# Main.net
KiCad netlist of a schematic drawn in Altium Designer
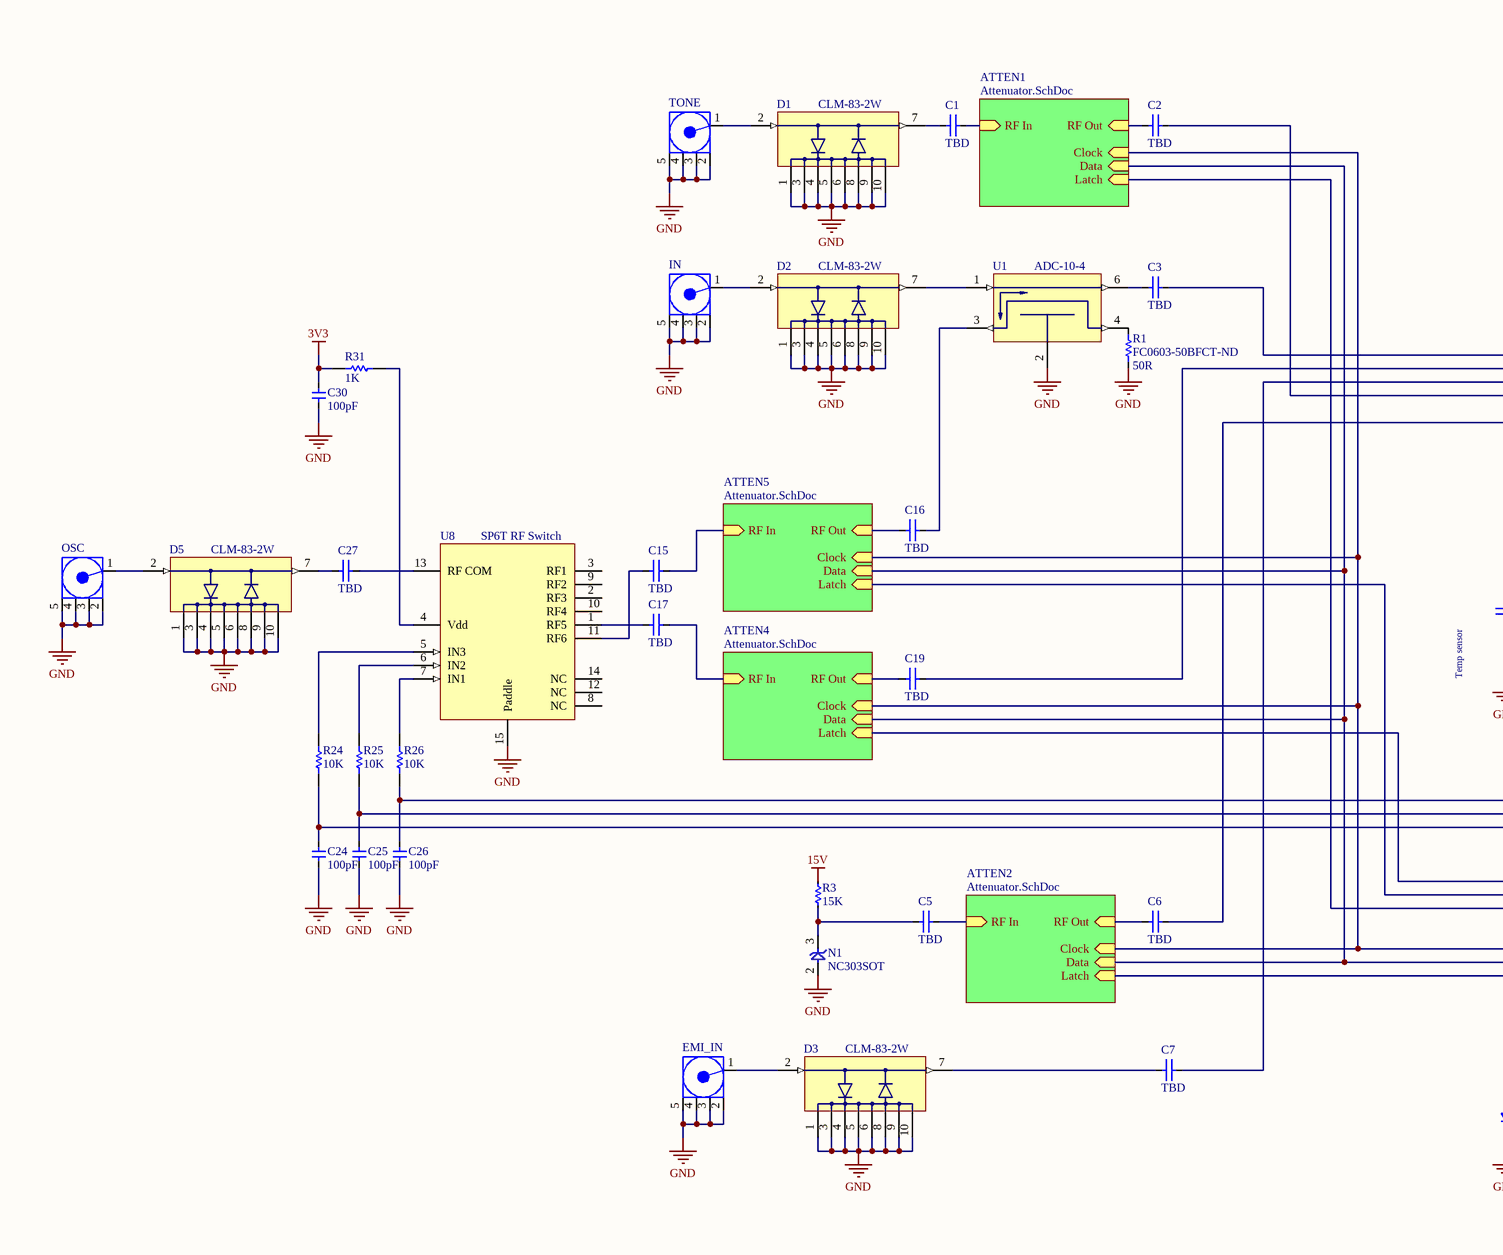
[diagram p0: Main.SchDoc, left]
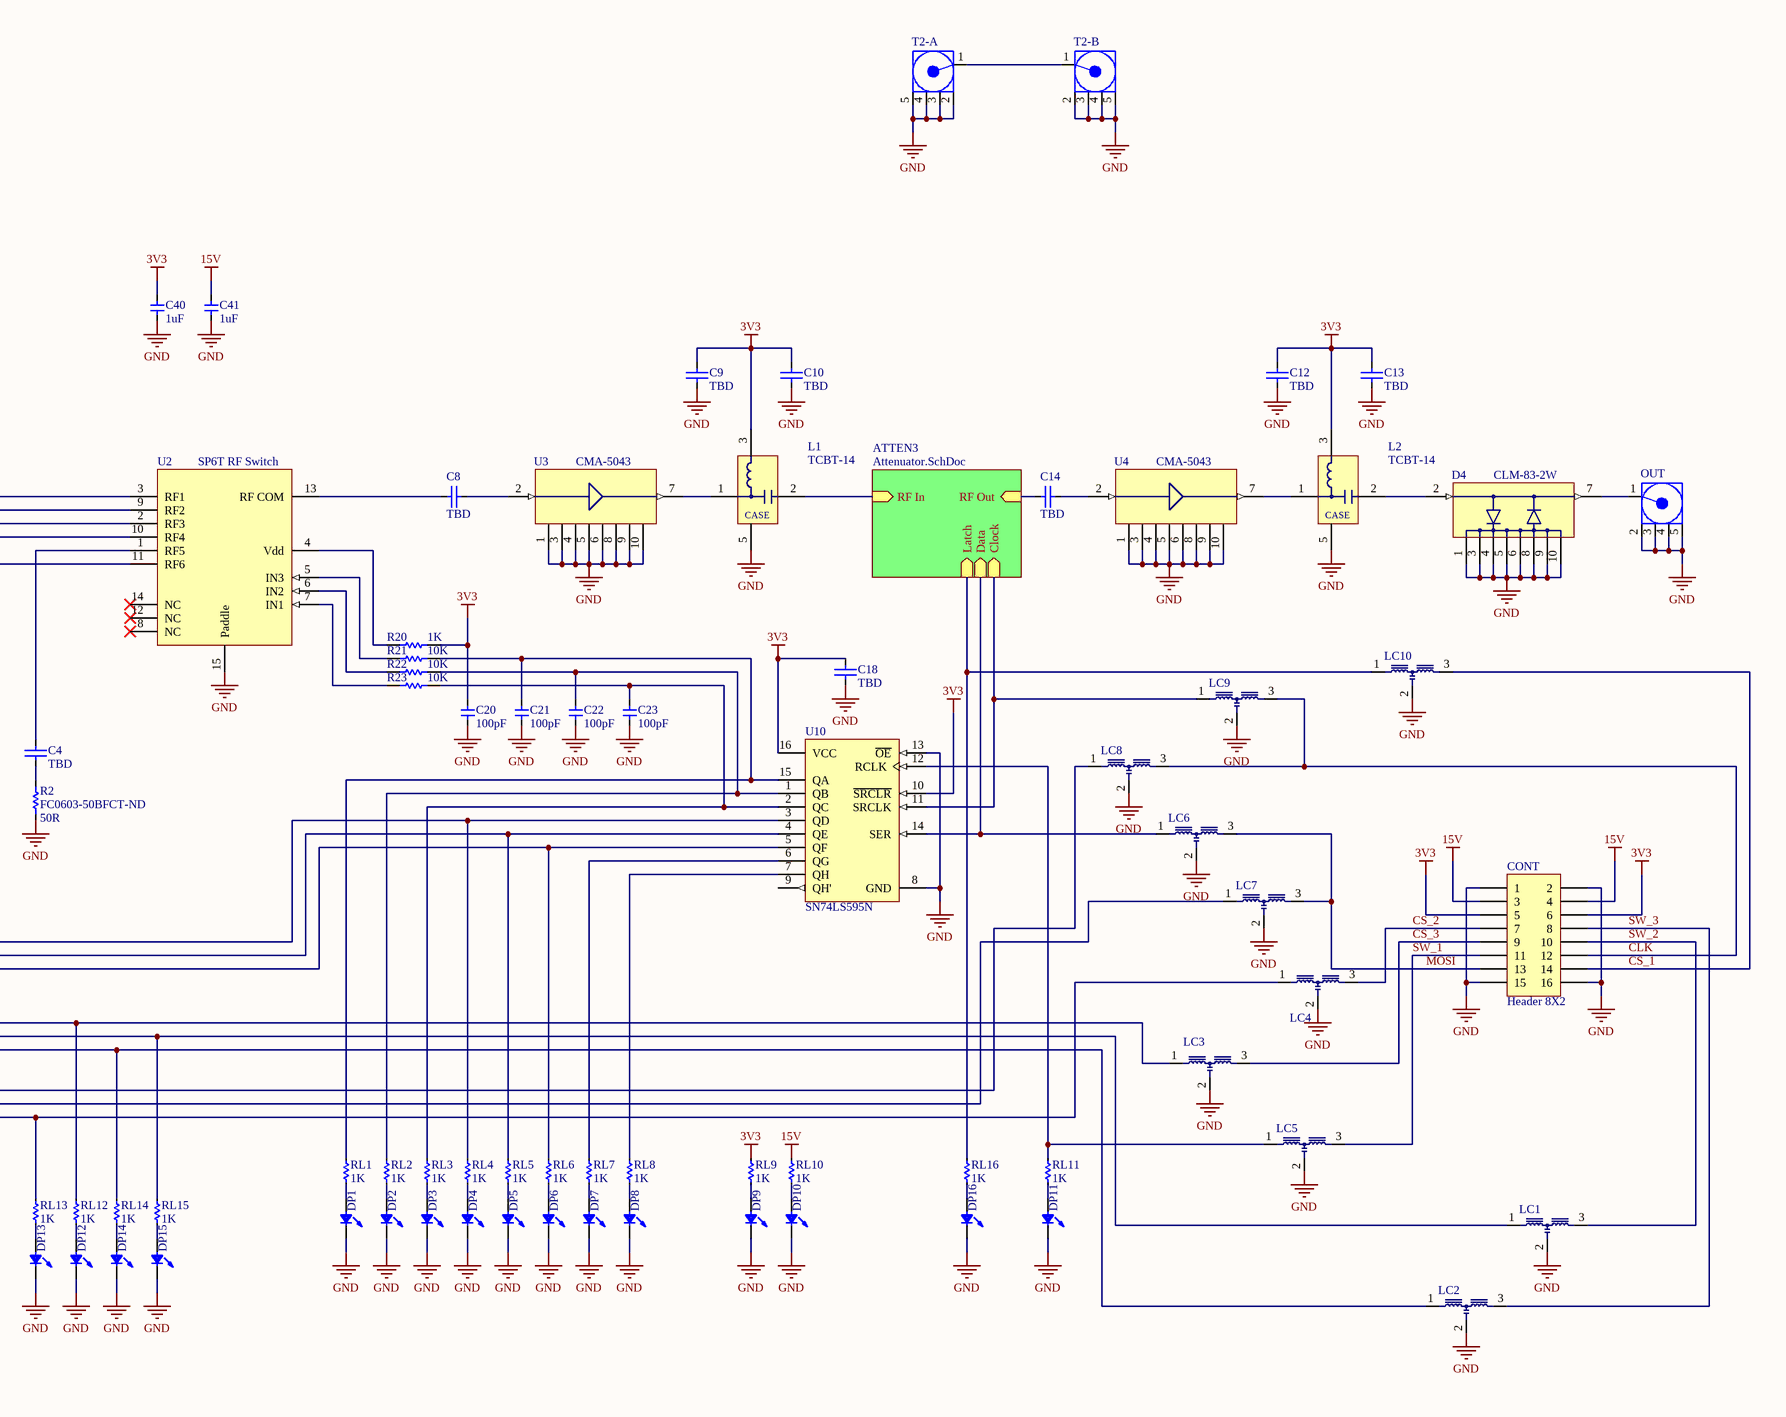
[diagram p1: Main.SchDoc, right]

(export (version "E")
  (design (tool "Eeschema 10.0.6"))
  (components
    (comp (ref "C1")
      (value "TBD")
      (footprint "0402C")
      (description "Capacitor")
      (fields (field (name "Comment") "Cap") (field (name "PUBLISHER") "Altium Limited"))
      (libsource (lib "Miscellaneous Devices") (part "Cap"))
    )
    (comp (ref "C2")
      (value "TBD")
      (footprint "0402C")
      (description "Capacitor")
      (fields (field (name "Comment") "Cap") (field (name "PUBLISHER") "Altium Limited"))
      (libsource (lib "Miscellaneous Devices") (part "Cap"))
    )
    (comp (ref "C3")
      (value "TBD")
      (footprint "0402C")
      (description "Capacitor")
      (fields (field (name "Comment") "Cap") (field (name "PUBLISHER") "Altium Limited"))
      (libsource (lib "Miscellaneous Devices") (part "Cap"))
    )
    (comp (ref "C4")
      (value "TBD")
      (footprint "0402C")
      (description "Capacitor")
      (fields (field (name "Comment") "Cap") (field (name "PUBLISHER") "Altium Limited"))
      (libsource (lib "Miscellaneous Devices") (part "Cap"))
    )
    (comp (ref "C5")
      (value "TBD")
      (footprint "0402C")
      (description "Capacitor")
      (fields (field (name "Comment") "Cap") (field (name "PUBLISHER") "Altium Limited"))
      (libsource (lib "Miscellaneous Devices") (part "Cap"))
    )
    (comp (ref "C6")
      (value "TBD")
      (footprint "0402C")
      (description "Capacitor")
      (fields (field (name "Comment") "Cap") (field (name "PUBLISHER") "Altium Limited"))
      (libsource (lib "Miscellaneous Devices") (part "Cap"))
    )
    (comp (ref "C7")
      (value "TBD")
      (footprint "0402C")
      (description "Capacitor")
      (fields (field (name "Comment") "Cap") (field (name "PUBLISHER") "Altium Limited"))
      (libsource (lib "Miscellaneous Devices") (part "Cap"))
    )
    (comp (ref "C8")
      (value "TBD")
      (footprint "0402C")
      (description "Capacitor")
      (fields (field (name "Comment") "Cap") (field (name "PUBLISHER") "Altium Limited"))
      (libsource (lib "Miscellaneous Devices") (part "Cap"))
    )
    (comp (ref "C9")
      (value "TBD")
      (footprint "0805C")
      (description "Capacitor")
      (fields (field (name "Comment") "Cap") (field (name "PUBLISHER") "Altium Limited"))
      (libsource (lib "Miscellaneous Devices") (part "Cap"))
    )
    (comp (ref "C10")
      (value "TBD")
      (footprint "0805C")
      (description "Capacitor")
      (fields (field (name "Comment") "Cap") (field (name "PUBLISHER") "Altium Limited"))
      (libsource (lib "Miscellaneous Devices") (part "Cap"))
    )
    (comp (ref "C12")
      (value "TBD")
      (footprint "0805C")
      (description "Capacitor")
      (fields (field (name "Comment") "Cap") (field (name "PUBLISHER") "Altium Limited"))
      (libsource (lib "Miscellaneous Devices") (part "Cap"))
    )
    (comp (ref "C13")
      (value "TBD")
      (footprint "0805C")
      (description "Capacitor")
      (fields (field (name "Comment") "Cap") (field (name "PUBLISHER") "Altium Limited"))
      (libsource (lib "Miscellaneous Devices") (part "Cap"))
    )
    (comp (ref "C14")
      (value "TBD")
      (footprint "0402C")
      (description "Capacitor")
      (fields (field (name "Comment") "Cap") (field (name "PUBLISHER") "Altium Limited"))
      (libsource (lib "Miscellaneous Devices") (part "Cap"))
    )
    (comp (ref "C15")
      (value "TBD")
      (footprint "0402C")
      (description "Capacitor")
      (fields (field (name "Comment") "Cap") (field (name "PUBLISHER") "Altium Limited"))
      (libsource (lib "Miscellaneous Devices") (part "Cap"))
    )
    (comp (ref "C16")
      (value "TBD")
      (footprint "0402C")
      (description "Capacitor")
      (fields (field (name "Comment") "Cap") (field (name "PUBLISHER") "Altium Limited"))
      (libsource (lib "Miscellaneous Devices") (part "Cap"))
    )
    (comp (ref "C17")
      (value "TBD")
      (footprint "0402C")
      (description "Capacitor")
      (fields (field (name "Comment") "Cap") (field (name "PUBLISHER") "Altium Limited"))
      (libsource (lib "Miscellaneous Devices") (part "Cap"))
    )
    (comp (ref "C18")
      (value "TBD")
      (footprint "0603C")
      (description "Capacitor")
      (fields (field (name "Comment") "Cap") (field (name "PUBLISHER") "Altium Limited"))
      (libsource (lib "Miscellaneous Devices") (part "Cap"))
    )
    (comp (ref "C19")
      (value "TBD")
      (footprint "0402C")
      (description "Capacitor")
      (fields (field (name "Comment") "Cap") (field (name "PUBLISHER") "Altium Limited"))
      (libsource (lib "Miscellaneous Devices") (part "Cap"))
    )
    (comp (ref "C20")
      (value "100pF")
      (footprint "0603C")
      (description "SMT Cap")
      (fields (field (name "PUBLISHER") "Altium Limited"))
      (libsource (lib "Miscellaneous Devices") (part "Cap - SMT Small"))
    )
    (comp (ref "C21")
      (value "100pF")
      (footprint "0603C")
      (description "SMT Cap")
      (fields (field (name "PUBLISHER") "Altium Limited"))
      (libsource (lib "Miscellaneous Devices") (part "Cap - SMT Small"))
    )
    (comp (ref "C22")
      (value "100pF")
      (footprint "0603C")
      (description "SMT Cap")
      (fields (field (name "PUBLISHER") "Altium Limited"))
      (libsource (lib "Miscellaneous Devices") (part "Cap - SMT Small"))
    )
    (comp (ref "C23")
      (value "100pF")
      (footprint "0603C")
      (description "SMT Cap")
      (fields (field (name "PUBLISHER") "Altium Limited"))
      (libsource (lib "Miscellaneous Devices") (part "Cap - SMT Small"))
    )
    (comp (ref "C24")
      (value "100pF")
      (footprint "0603C")
      (description "SMT Cap")
      (fields (field (name "PUBLISHER") "Altium Limited"))
      (libsource (lib "Miscellaneous Devices") (part "Cap - SMT Small"))
    )
    (comp (ref "C25")
      (value "100pF")
      (footprint "0603C")
      (description "SMT Cap")
      (fields (field (name "PUBLISHER") "Altium Limited"))
      (libsource (lib "Miscellaneous Devices") (part "Cap - SMT Small"))
    )
    (comp (ref "C26")
      (value "100pF")
      (footprint "0603C")
      (description "SMT Cap")
      (fields (field (name "PUBLISHER") "Altium Limited"))
      (libsource (lib "Miscellaneous Devices") (part "Cap - SMT Small"))
    )
    (comp (ref "C27")
      (value "TBD")
      (footprint "0402C")
      (description "Capacitor")
      (fields (field (name "Comment") "Cap") (field (name "PUBLISHER") "Altium Limited"))
      (libsource (lib "Miscellaneous Devices") (part "Cap"))
    )
    (comp (ref "C30")
      (value "100pF")
      (footprint "0603C")
      (description "SMT Cap")
      (fields (field (name "PUBLISHER") "Altium Limited"))
      (libsource (lib "Miscellaneous Devices") (part "Cap - SMT Small"))
    )
    (comp (ref "C40")
      (value "1uF")
      (footprint "V")
      (description "SMT Cap")
      (fields (field (name "PUBLISHER") "Altium Limited"))
      (libsource (lib "Miscellaneous Devices") (part "Cap - SMT Small"))
    )
    (comp (ref "C41")
      (value "1uF")
      (footprint "V")
      (description "SMT Cap")
      (fields (field (name "PUBLISHER") "Altium Limited"))
      (libsource (lib "Miscellaneous Devices") (part "Cap - SMT Small"))
    )
    (comp (ref "CONT")
      (value "Header 8X2")
      (footprint "SMT 16-pin rectangular header")
      (description "Header, 8-Pin, Dual row")
      (fields (field (name "PUBLISHER") "Altium Limited"))
      (libsource (lib "Miscellaneous Connectors") (part "Header 8X2"))
    )
    (comp (ref "D1")
      (value "CLM-83-2W")
      (footprint "DL1721")
      (description "+12 to +32 dBm RF Limiter")
      (libsource (lib "RF Components") (part "CLM-83-2W"))
    )
    (comp (ref "D2")
      (value "CLM-83-2W")
      (footprint "DL1721")
      (description "+12 to +32 dBm RF Limiter")
      (libsource (lib "RF Components") (part "CLM-83-2W"))
    )
    (comp (ref "D3")
      (value "CLM-83-2W")
      (footprint "DL1721")
      (description "+12 to +32 dBm RF Limiter")
      (libsource (lib "RF Components") (part "CLM-83-2W"))
    )
    (comp (ref "D4")
      (value "CLM-83-2W")
      (footprint "DL1721")
      (description "+12 to +32 dBm RF Limiter")
      (libsource (lib "RF Components") (part "CLM-83-2W"))
    )
    (comp (ref "D5")
      (value "CLM-83-2W")
      (footprint "DL1721")
      (description "+12 to +32 dBm RF Limiter")
      (libsource (lib "RF Components") (part "CLM-83-2W"))
    )
    (comp (ref "DP1")
      (value "LED0")
      (footprint "0603 SMT LED")
      (description "T 1 3/4 LED")
      (fields (field (name "PUBLISHER") "Altium Limited"))
      (libsource (lib "Miscellaneous Devices") (part "LED0"))
    )
    (comp (ref "DP2")
      (value "LED0")
      (footprint "0603 SMT LED")
      (description "T 1 3/4 LED")
      (fields (field (name "PUBLISHER") "Altium Limited"))
      (libsource (lib "Miscellaneous Devices") (part "LED0"))
    )
    (comp (ref "DP3")
      (value "LED0")
      (footprint "0603 SMT LED")
      (description "T 1 3/4 LED")
      (fields (field (name "PUBLISHER") "Altium Limited"))
      (libsource (lib "Miscellaneous Devices") (part "LED0"))
    )
    (comp (ref "DP4")
      (value "LED0")
      (footprint "0603 SMT LED")
      (description "T 1 3/4 LED")
      (fields (field (name "PUBLISHER") "Altium Limited"))
      (libsource (lib "Miscellaneous Devices") (part "LED0"))
    )
    (comp (ref "DP5")
      (value "LED0")
      (footprint "0603 SMT LED")
      (description "T 1 3/4 LED")
      (fields (field (name "PUBLISHER") "Altium Limited"))
      (libsource (lib "Miscellaneous Devices") (part "LED0"))
    )
    (comp (ref "DP6")
      (value "LED0")
      (footprint "0603 SMT LED")
      (description "T 1 3/4 LED")
      (fields (field (name "PUBLISHER") "Altium Limited"))
      (libsource (lib "Miscellaneous Devices") (part "LED0"))
    )
    (comp (ref "DP7")
      (value "LED0")
      (footprint "0603 SMT LED")
      (description "T 1 3/4 LED")
      (fields (field (name "PUBLISHER") "Altium Limited"))
      (libsource (lib "Miscellaneous Devices") (part "LED0"))
    )
    (comp (ref "DP8")
      (value "LED0")
      (footprint "0603 SMT LED")
      (description "T 1 3/4 LED")
      (fields (field (name "PUBLISHER") "Altium Limited"))
      (libsource (lib "Miscellaneous Devices") (part "LED0"))
    )
    (comp (ref "DP9")
      (value "LED0")
      (footprint "0603 SMT LED")
      (description "T 1 3/4 LED")
      (fields (field (name "PUBLISHER") "Altium Limited"))
      (libsource (lib "Miscellaneous Devices") (part "LED0"))
    )
    (comp (ref "DP10")
      (value "LED0")
      (footprint "0603 SMT LED")
      (description "T 1 3/4 LED")
      (fields (field (name "PUBLISHER") "Altium Limited"))
      (libsource (lib "Miscellaneous Devices") (part "LED0"))
    )
    (comp (ref "DP11")
      (value "LED0")
      (footprint "0603 SMT LED")
      (description "T 1 3/4 LED")
      (fields (field (name "PUBLISHER") "Altium Limited"))
      (libsource (lib "Miscellaneous Devices") (part "LED0"))
    )
    (comp (ref "DP12")
      (value "LED0")
      (footprint "0603 SMT LED")
      (description "T 1 3/4 LED")
      (fields (field (name "PUBLISHER") "Altium Limited"))
      (libsource (lib "Miscellaneous Devices") (part "LED0"))
    )
    (comp (ref "DP13")
      (value "LED0")
      (footprint "0603 SMT LED")
      (description "T 1 3/4 LED")
      (fields (field (name "PUBLISHER") "Altium Limited"))
      (libsource (lib "Miscellaneous Devices") (part "LED0"))
    )
    (comp (ref "DP14")
      (value "LED0")
      (footprint "0603 SMT LED")
      (description "T 1 3/4 LED")
      (fields (field (name "PUBLISHER") "Altium Limited"))
      (libsource (lib "Miscellaneous Devices") (part "LED0"))
    )
    (comp (ref "DP15")
      (value "LED0")
      (footprint "0603 SMT LED")
      (description "T 1 3/4 LED")
      (fields (field (name "PUBLISHER") "Altium Limited"))
      (libsource (lib "Miscellaneous Devices") (part "LED0"))
    )
    (comp (ref "DP16")
      (value "LED0")
      (footprint "0603 SMT LED")
      (description "T 1 3/4 LED")
      (fields (field (name "PUBLISHER") "Altium Limited"))
      (libsource (lib "Miscellaneous Devices") (part "LED0"))
    )
    (comp (ref "EMI_IN")
      (value "COAX-M")
      (footprint "SMT RA SMA Connector")
      (description "RF Coaxial PCB Connector, MMCX; Thru-Hole, Vertical Mount Plug,  50 Ohm Impedance")
      (fields (field (name "PUBLISHER") "Altium Limited"))
      (libsource (lib "Miscellaneous Connectors") (part "COAX-M"))
    )
    (comp (ref "IN")
      (value "COAX-M")
      (footprint "SMT RA SMA Connector")
      (description "RF Coaxial PCB Connector, MMCX; Thru-Hole, Vertical Mount Plug,  50 Ohm Impedance")
      (fields (field (name "PUBLISHER") "Altium Limited"))
      (libsource (lib "Miscellaneous Connectors") (part "COAX-M"))
    )
    (comp (ref "L1")
      (value "TCBT-14")
      (footprint "GU1414")
      (description "Surface Mount 10 MHz to 10 GHz Bias Tee")
      (libsource (lib "RF Components") (part "TCBT-14"))
    )
    (comp (ref "L2")
      (value "TCBT-14")
      (footprint "GU1414")
      (description "Surface Mount 10 MHz to 10 GHz Bias Tee")
      (libsource (lib "RF Components") (part "TCBT-14"))
    )
    (comp (ref "LC1")
      (value "MEM2012F")
      (footprint "MEM2012S LC Filter")
      (description "Signal Line 3-terminal Filters")
      (libsource (lib "Unsorted") (part "MEM2012F - Signal Filter"))
    )
    (comp (ref "LC2")
      (value "MEM2012F")
      (footprint "MEM2012S LC Filter")
      (description "Signal Line 3-terminal Filters")
      (libsource (lib "Unsorted") (part "MEM2012F - Signal Filter"))
    )
    (comp (ref "LC3")
      (value "MEM2012F")
      (footprint "MEM2012S LC Filter")
      (description "Signal Line 3-terminal Filters")
      (libsource (lib "Unsorted") (part "MEM2012F - Signal Filter"))
    )
    (comp (ref "LC4")
      (value "MEM2012F")
      (footprint "MEM2012S LC Filter")
      (description "Signal Line 3-terminal Filters")
      (libsource (lib "Unsorted") (part "MEM2012F - Signal Filter"))
    )
    (comp (ref "LC5")
      (value "MEM2012F")
      (footprint "MEM2012S LC Filter")
      (description "Signal Line 3-terminal Filters")
      (libsource (lib "Unsorted") (part "MEM2012F - Signal Filter"))
    )
    (comp (ref "LC6")
      (value "MEM2012F")
      (footprint "MEM2012S LC Filter")
      (description "Signal Line 3-terminal Filters")
      (libsource (lib "Unsorted") (part "MEM2012F - Signal Filter"))
    )
    (comp (ref "LC7")
      (value "MEM2012F")
      (footprint "MEM2012S LC Filter")
      (description "Signal Line 3-terminal Filters")
      (libsource (lib "Unsorted") (part "MEM2012F - Signal Filter"))
    )
    (comp (ref "LC8")
      (value "MEM2012F")
      (footprint "MEM2012S LC Filter")
      (description "Signal Line 3-terminal Filters")
      (libsource (lib "Unsorted") (part "MEM2012F - Signal Filter"))
    )
    (comp (ref "LC9")
      (value "MEM2012F")
      (footprint "MEM2012S LC Filter")
      (description "Signal Line 3-terminal Filters")
      (libsource (lib "Unsorted") (part "MEM2012F - Signal Filter"))
    )
    (comp (ref "LC10")
      (value "MEM2012F")
      (footprint "MEM2012S LC Filter")
      (description "Signal Line 3-terminal Filters")
      (libsource (lib "Unsorted") (part "MEM2012F - Signal Filter"))
    )
    (comp (ref "N1")
      (value "NC303SOT")
      (footprint "SOT323-3AN")
      (description "SMT Noise Diode")
      (libsource (lib "RF Components") (part "NC303SOT"))
    )
    (comp (ref "OSC")
      (value "COAX-M")
      (footprint "SMT RA SMA Connector")
      (description "RF Coaxial PCB Connector, MMCX; Thru-Hole, Vertical Mount Plug,  50 Ohm Impedance")
      (fields (field (name "PUBLISHER") "Altium Limited"))
      (libsource (lib "Miscellaneous Connectors") (part "COAX-M"))
    )
    (comp (ref "OUT")
      (value "COAX-M")
      (footprint "SMT RA SMA Connector")
      (description "RF Coaxial PCB Connector, MMCX; Thru-Hole, Vertical Mount Plug,  50 Ohm Impedance")
      (fields (field (name "PUBLISHER") "Altium Limited"))
      (libsource (lib "Miscellaneous Connectors") (part "COAX-M"))
    )
    (comp (ref "R1")
      (value "FC0603-50BFCT-ND")
      (footprint "0603R")
      (fields (field (name "ALTIUM_VALUE") "50R") (field (name "PUBLISHER") "Altium Limited"))
      (libsource (lib "") (part "Res Semi_1"))
    )
    (comp (ref "R2")
      (value "FC0603-50BFCT-ND")
      (footprint "0603R")
      (fields (field (name "ALTIUM_VALUE") "50R") (field (name "PUBLISHER") "Altium Limited"))
      (libsource (lib "") (part "Res Semi_1"))
    )
    (comp (ref "R3")
      (value "15K")
      (footprint "1206R")
      (description "Semiconductor Resistor")
      (fields (field (name "Comment") "Res Semi Small") (field (name "PUBLISHER") "Altium Limited"))
      (libsource (lib "Miscellaneous Devices") (part "Res Semi Small"))
    )
    (comp (ref "R20")
      (value "1K")
      (footprint "0603R")
      (description "Semiconductor Resistor")
      (fields (field (name "Comment") "RES Semi") (field (name "PUBLISHER") "Altium Limited"))
      (libsource (lib "Miscellaneous Devices") (part "Res Semi"))
    )
    (comp (ref "R21")
      (value "10K")
      (footprint "0603R")
      (description "Semiconductor Resistor")
      (fields (field (name "Comment") "RES Semi") (field (name "PUBLISHER") "Altium Limited"))
      (libsource (lib "Miscellaneous Devices") (part "Res Semi"))
    )
    (comp (ref "R22")
      (value "10K")
      (footprint "0603R")
      (description "Semiconductor Resistor")
      (fields (field (name "Comment") "RES Semi") (field (name "PUBLISHER") "Altium Limited"))
      (libsource (lib "Miscellaneous Devices") (part "Res Semi"))
    )
    (comp (ref "R23")
      (value "10K")
      (footprint "0603R")
      (description "Semiconductor Resistor")
      (fields (field (name "Comment") "RES Semi") (field (name "PUBLISHER") "Altium Limited"))
      (libsource (lib "Miscellaneous Devices") (part "Res Semi"))
    )
    (comp (ref "R24")
      (value "10K")
      (footprint "0603R")
      (description "Semiconductor Resistor")
      (fields (field (name "Comment") "RES Semi") (field (name "PUBLISHER") "Altium Limited"))
      (libsource (lib "Miscellaneous Devices") (part "Res Semi"))
    )
    (comp (ref "R25")
      (value "10K")
      (footprint "0603R")
      (description "Semiconductor Resistor")
      (fields (field (name "Comment") "RES Semi") (field (name "PUBLISHER") "Altium Limited"))
      (libsource (lib "Miscellaneous Devices") (part "Res Semi"))
    )
    (comp (ref "R26")
      (value "10K")
      (footprint "0603R")
      (description "Semiconductor Resistor")
      (fields (field (name "Comment") "RES Semi") (field (name "PUBLISHER") "Altium Limited"))
      (libsource (lib "Miscellaneous Devices") (part "Res Semi"))
    )
    (comp (ref "R31")
      (value "1K")
      (footprint "0603R")
      (description "Semiconductor Resistor")
      (fields (field (name "Comment") "RES Semi") (field (name "PUBLISHER") "Altium Limited"))
      (libsource (lib "Miscellaneous Devices") (part "Res Semi"))
    )
    (comp (ref "RL1")
      (value "1K")
      (footprint "0603R")
      (description "Semiconductor Resistor")
      (fields (field (name "Comment") "Res Semi Small") (field (name "PUBLISHER") "Altium Limited"))
      (libsource (lib "Miscellaneous Devices") (part "Res Semi Small"))
    )
    (comp (ref "RL2")
      (value "1K")
      (footprint "0603R")
      (description "Semiconductor Resistor")
      (fields (field (name "Comment") "Res Semi Small") (field (name "PUBLISHER") "Altium Limited"))
      (libsource (lib "Miscellaneous Devices") (part "Res Semi Small"))
    )
    (comp (ref "RL3")
      (value "1K")
      (footprint "0603R")
      (description "Semiconductor Resistor")
      (fields (field (name "Comment") "Res Semi Small") (field (name "PUBLISHER") "Altium Limited"))
      (libsource (lib "Miscellaneous Devices") (part "Res Semi Small"))
    )
    (comp (ref "RL4")
      (value "1K")
      (footprint "0603R")
      (description "Semiconductor Resistor")
      (fields (field (name "Comment") "Res Semi Small") (field (name "PUBLISHER") "Altium Limited"))
      (libsource (lib "Miscellaneous Devices") (part "Res Semi Small"))
    )
    (comp (ref "RL5")
      (value "1K")
      (footprint "0603R")
      (description "Semiconductor Resistor")
      (fields (field (name "Comment") "Res Semi Small") (field (name "PUBLISHER") "Altium Limited"))
      (libsource (lib "Miscellaneous Devices") (part "Res Semi Small"))
    )
    (comp (ref "RL6")
      (value "1K")
      (footprint "0603R")
      (description "Semiconductor Resistor")
      (fields (field (name "Comment") "Res Semi Small") (field (name "PUBLISHER") "Altium Limited"))
      (libsource (lib "Miscellaneous Devices") (part "Res Semi Small"))
    )
    (comp (ref "RL7")
      (value "1K")
      (footprint "0603R")
      (description "Semiconductor Resistor")
      (fields (field (name "Comment") "Res Semi Small") (field (name "PUBLISHER") "Altium Limited"))
      (libsource (lib "Miscellaneous Devices") (part "Res Semi Small"))
    )
    (comp (ref "RL8")
      (value "1K")
      (footprint "0603R")
      (description "Semiconductor Resistor")
      (fields (field (name "Comment") "Res Semi Small") (field (name "PUBLISHER") "Altium Limited"))
      (libsource (lib "Miscellaneous Devices") (part "Res Semi Small"))
    )
    (comp (ref "RL9")
      (value "1K")
      (footprint "0603R")
      (description "Semiconductor Resistor")
      (fields (field (name "Comment") "Res Semi Small") (field (name "PUBLISHER") "Altium Limited"))
      (libsource (lib "Miscellaneous Devices") (part "Res Semi Small"))
    )
    (comp (ref "RL10")
      (value "1K")
      (footprint "0603R")
      (description "Semiconductor Resistor")
      (fields (field (name "Comment") "Res Semi Small") (field (name "PUBLISHER") "Altium Limited"))
      (libsource (lib "Miscellaneous Devices") (part "Res Semi Small"))
    )
    (comp (ref "RL11")
      (value "1K")
      (footprint "0603R")
      (description "Semiconductor Resistor")
      (fields (field (name "Comment") "Res Semi Small") (field (name "PUBLISHER") "Altium Limited"))
      (libsource (lib "Miscellaneous Devices") (part "Res Semi Small"))
    )
    (comp (ref "RL12")
      (value "1K")
      (footprint "0603R")
      (description "Semiconductor Resistor")
      (fields (field (name "Comment") "Res Semi Small") (field (name "PUBLISHER") "Altium Limited"))
      (libsource (lib "Miscellaneous Devices") (part "Res Semi Small"))
    )
    (comp (ref "RL13")
      (value "1K")
      (footprint "0603R")
      (description "Semiconductor Resistor")
      (fields (field (name "Comment") "Res Semi Small") (field (name "PUBLISHER") "Altium Limited"))
      (libsource (lib "Miscellaneous Devices") (part "Res Semi Small"))
    )
    (comp (ref "RL14")
      (value "1K")
      (footprint "0603R")
      (description "Semiconductor Resistor")
      (fields (field (name "Comment") "Res Semi Small") (field (name "PUBLISHER") "Altium Limited"))
      (libsource (lib "Miscellaneous Devices") (part "Res Semi Small"))
    )
    (comp (ref "RL15")
      (value "1K")
      (footprint "0603R")
      (description "Semiconductor Resistor")
      (fields (field (name "Comment") "Res Semi Small") (field (name "PUBLISHER") "Altium Limited"))
      (libsource (lib "Miscellaneous Devices") (part "Res Semi Small"))
    )
    (comp (ref "RL16")
      (value "1K")
      (footprint "0603R")
      (description "Semiconductor Resistor")
      (fields (field (name "Comment") "Res Semi Small") (field (name "PUBLISHER") "Altium Limited"))
      (libsource (lib "Miscellaneous Devices") (part "Res Semi Small"))
    )
    (comp (ref "T2-A")
      (value "COAX-M")
      (footprint "SMT RA SMA Connector")
      (description "RF Coaxial PCB Connector, MMCX; Thru-Hole, Vertical Mount Plug,  50 Ohm Impedance")
      (fields (field (name "PUBLISHER") "Altium Limited"))
      (libsource (lib "Miscellaneous Connectors") (part "COAX-M"))
    )
    (comp (ref "T2-B")
      (value "COAX-M")
      (footprint "SMT RA SMA Connector")
      (description "RF Coaxial PCB Connector, MMCX; Thru-Hole, Vertical Mount Plug,  50 Ohm Impedance")
      (fields (field (name "PUBLISHER") "Altium Limited"))
      (libsource (lib "Miscellaneous Connectors") (part "COAX-M"))
    )
    (comp (ref "TONE")
      (value "COAX-M")
      (footprint "SMT RA SMA Connector")
      (description "RF Coaxial PCB Connector, MMCX; Thru-Hole, Vertical Mount Plug,  50 Ohm Impedance")
      (fields (field (name "PUBLISHER") "Altium Limited"))
      (libsource (lib "Miscellaneous Connectors") (part "COAX-M"))
    )
    (comp (ref "U1")
      (value "ADC-10-4")
      (footprint "CD542")
      (description "Surface Mount Directional Coupler")
      (libsource (lib "RF Components") (part "ADC-10-4"))
    )
    (comp (ref "U2")
      (value "SP6T RF Switch")
      (footprint "MT1817")
      (description "SP6T RF Switch 50Ω 10 to 2700 MHz")
      (libsource (lib "") (part "JSW6-33DR+_1"))
    )
    (comp (ref "U3")
      (value "CMA-5043")
      (footprint "DL1721")
      (description "Low Noise, High IP3 Monolithic Amplifier")
      (libsource (lib "RF Components") (part "CMA-5043"))
    )
    (comp (ref "U4")
      (value "CMA-5043")
      (footprint "DL1721")
      (description "Low Noise, High IP3 Monolithic Amplifier")
      (libsource (lib "RF Components") (part "CMA-5043"))
    )
    (comp (ref "U8")
      (value "SP6T RF Switch")
      (footprint "MT1817")
      (description "SP6T RF Switch 50Ω 10 to 2700 MHz")
      (libsource (lib "RF Components") (part "JSW6-33DR+"))
    )
    (comp (ref "U10")
      (value "SN74LS595N")
      (footprint "SOIC127P602-16BN")
      (description "8-Bit Shift Register with Output Latch")
      (fields (field (name "PUBLISHER") "Altium Limited"))
      (libsource (lib "TI Logic Register") (part "SN74LS595N"))
    )
  )
  (nets
    (net (code "1") (name "/CLK") (class "Default")
      (node (ref "CONT") (pin "12") (pinfunction "12_12") (pintype "passive"))
      (node (ref "LC8") (pin "3") (pinfunction "3_3") (pintype "passive"))
      (node (ref "LC9") (pin "3") (pinfunction "3_3") (pintype "passive"))
    )
    (net (code "2") (name "/CS_1") (class "Default")
      (node (ref "CONT") (pin "14") (pinfunction "14_14") (pintype "passive"))
      (node (ref "LC10") (pin "3") (pinfunction "3_3") (pintype "passive"))
    )
    (net (code "3") (name "/CS_2") (class "Default")
      (node (ref "CONT") (pin "7") (pinfunction "7_7") (pintype "passive"))
      (node (ref "LC4") (pin "3") (pinfunction "3_3") (pintype "passive"))
    )
    (net (code "4") (name "/CS_3") (class "Default")
      (node (ref "CONT") (pin "9") (pinfunction "9_9") (pintype "passive"))
      (node (ref "LC3") (pin "3") (pinfunction "3_3") (pintype "passive"))
    )
    (net (code "5") (name "/Clock") (class "Default")
      (node (ref "LC8") (pin "1") (pinfunction "1_1") (pintype "passive"))
    )
    (net (code "6") (name "/Clock_1") (class "Default")
      (node (ref "LC9") (pin "1") (pinfunction "1_1") (pintype "passive"))
      (node (ref "U10") (pin "11") (pinfunction "SRCLK_11") (pintype "input"))
    )
    (net (code "7") (name "/Data") (class "Default")
      (node (ref "LC7") (pin "1") (pinfunction "1_1") (pintype "passive"))
    )
    (net (code "8") (name "/Data_1") (class "Default")
      (node (ref "LC6") (pin "1") (pinfunction "1_1") (pintype "passive"))
      (node (ref "U10") (pin "14") (pinfunction "SER_14") (pintype "input"))
    )
    (net (code "9") (name "/Latch") (class "Default")
      (node (ref "LC2") (pin "1") (pinfunction "1_1") (pintype "passive"))
      (node (ref "RL14") (pin "1") (pinfunction "1_1") (pintype "passive"))
    )
    (net (code "10") (name "/Latch_1") (class "Default")
      (node (ref "LC10") (pin "1") (pinfunction "1_1") (pintype "passive"))
      (node (ref "RL16") (pin "1") (pinfunction "1_1") (pintype "passive"))
    )
    (net (code "11") (name "/Latch_2") (class "Default")
      (node (ref "LC4") (pin "1") (pinfunction "1_1") (pintype "passive"))
      (node (ref "RL13") (pin "1") (pinfunction "1_1") (pintype "passive"))
    )
    (net (code "12") (name "/Latch_3") (class "Default")
      (node (ref "LC3") (pin "1") (pinfunction "1_1") (pintype "passive"))
      (node (ref "RL12") (pin "1") (pinfunction "1_1") (pintype "passive"))
    )
    (net (code "13") (name "/Latch_4") (class "Default")
      (node (ref "LC1") (pin "1") (pinfunction "1_1") (pintype "passive"))
      (node (ref "RL15") (pin "1") (pinfunction "1_1") (pintype "passive"))
    )
    (net (code "14") (name "/MOSI") (class "Default")
      (node (ref "CONT") (pin "13") (pinfunction "13_13") (pintype "passive"))
      (node (ref "LC6") (pin "3") (pinfunction "3_3") (pintype "passive"))
      (node (ref "LC7") (pin "3") (pinfunction "3_3") (pintype "passive"))
    )
    (net (code "15") (name "/RF In") (class "Default")
      (node (ref "C1") (pin "2") (pinfunction "2_2") (pintype "passive"))
    )
    (net (code "16") (name "/RF In_1") (class "Default")
      (node (ref "L1") (pin "2") (pinfunction "RF_2") (pintype "passive"))
    )
    (net (code "17") (name "/RF In_2") (class "Default")
      (node (ref "C17") (pin "2") (pinfunction "2_2") (pintype "passive"))
    )
    (net (code "18") (name "/RF In_3") (class "Default")
      (node (ref "C15") (pin "2") (pinfunction "2_2") (pintype "passive"))
    )
    (net (code "19") (name "/RF In_4") (class "Default")
      (node (ref "C5") (pin "2") (pinfunction "2_2") (pintype "passive"))
    )
    (net (code "20") (name "/RF Out") (class "Default")
      (node (ref "C2") (pin "1") (pinfunction "1_1") (pintype "passive"))
    )
    (net (code "21") (name "/RF Out_1") (class "Default")
      (node (ref "C14") (pin "1") (pinfunction "1_1") (pintype "passive"))
    )
    (net (code "22") (name "/RF Out_2") (class "Default")
      (node (ref "C16") (pin "1") (pinfunction "1_1") (pintype "passive"))
    )
    (net (code "23") (name "/RF Out_3") (class "Default")
      (node (ref "C19") (pin "1") (pinfunction "1_1") (pintype "passive"))
    )
    (net (code "24") (name "/RF Out_4") (class "Default")
      (node (ref "C6") (pin "1") (pinfunction "1_1") (pintype "passive"))
    )
    (net (code "25") (name "/SW_1") (class "Default")
      (node (ref "CONT") (pin "11") (pinfunction "11_11") (pintype "passive"))
      (node (ref "LC5") (pin "3") (pinfunction "3_3") (pintype "passive"))
    )
    (net (code "26") (name "/SW_2") (class "Default")
      (node (ref "CONT") (pin "10") (pinfunction "10_10") (pintype "passive"))
      (node (ref "LC1") (pin "3") (pinfunction "3_3") (pintype "passive"))
    )
    (net (code "27") (name "/SW_3") (class "Default")
      (node (ref "CONT") (pin "8") (pinfunction "8_8") (pintype "passive"))
      (node (ref "LC2") (pin "3") (pinfunction "3_3") (pintype "passive"))
    )
    (net (code "28") (name "3V3") (class "Default")
      (node (ref "C10") (pin "2") (pinfunction "2_2") (pintype "passive"))
      (node (ref "C12") (pin "2") (pinfunction "2_2") (pintype "passive"))
      (node (ref "C13") (pin "2") (pinfunction "2_2") (pintype "passive"))
      (node (ref "C18") (pin "2") (pinfunction "2_2") (pintype "passive"))
      (node (ref "C20") (pin "2") (pinfunction "2_2") (pintype "passive"))
      (node (ref "C30") (pin "2") (pinfunction "2_2") (pintype "passive"))
      (node (ref "C40") (pin "1") (pinfunction "1_1") (pintype "passive"))
      (node (ref "C9") (pin "2") (pinfunction "2_2") (pintype "passive"))
      (node (ref "CONT") (pin "5") (pinfunction "5_5") (pintype "passive"))
      (node (ref "CONT") (pin "6") (pinfunction "6_6") (pintype "passive"))
      (node (ref "L1") (pin "3") (pinfunction "DC_3") (pintype "passive"))
      (node (ref "L2") (pin "3") (pinfunction "DC_3") (pintype "passive"))
      (node (ref "R20") (pin "2") (pinfunction "2_2") (pintype "passive"))
      (node (ref "R31") (pin "2") (pinfunction "2_2") (pintype "passive"))
      (node (ref "RL9") (pin "1") (pinfunction "1_1") (pintype "passive"))
      (node (ref "U10") (pin "10") (pinfunction "~{SRCLR}_10") (pintype "input"))
      (node (ref "U10") (pin "16") (pinfunction "VCC_16") (pintype "power_in"))
    )
    (net (code "29") (name "15V") (class "Default")
      (node (ref "C41") (pin "1") (pinfunction "1_1") (pintype "passive"))
      (node (ref "CONT") (pin "3") (pinfunction "3_3") (pintype "passive"))
      (node (ref "CONT") (pin "4") (pinfunction "4_4") (pintype "passive"))
      (node (ref "R3") (pin "2") (pinfunction "2_2") (pintype "passive"))
      (node (ref "RL10") (pin "1") (pinfunction "1_1") (pintype "passive"))
    )
    (net (code "30") (name "GND") (class "Default")
      (node (ref "C10") (pin "1") (pinfunction "1_1") (pintype "passive"))
      (node (ref "C12") (pin "1") (pinfunction "1_1") (pintype "passive"))
      (node (ref "C13") (pin "1") (pinfunction "1_1") (pintype "passive"))
      (node (ref "C18") (pin "1") (pinfunction "1_1") (pintype "passive"))
      (node (ref "C20") (pin "1") (pinfunction "1_1") (pintype "passive"))
      (node (ref "C21") (pin "1") (pinfunction "1_1") (pintype "passive"))
      (node (ref "C22") (pin "1") (pinfunction "1_1") (pintype "passive"))
      (node (ref "C23") (pin "1") (pinfunction "1_1") (pintype "passive"))
      (node (ref "C24") (pin "1") (pinfunction "1_1") (pintype "passive"))
      (node (ref "C25") (pin "1") (pinfunction "1_1") (pintype "passive"))
      (node (ref "C26") (pin "1") (pinfunction "1_1") (pintype "passive"))
      (node (ref "C30") (pin "1") (pinfunction "1_1") (pintype "passive"))
      (node (ref "C40") (pin "2") (pinfunction "2_2") (pintype "passive"))
      (node (ref "C41") (pin "2") (pinfunction "2_2") (pintype "passive"))
      (node (ref "C9") (pin "1") (pinfunction "1_1") (pintype "passive"))
      (node (ref "CONT") (pin "1") (pinfunction "1_1") (pintype "passive"))
      (node (ref "CONT") (pin "15") (pinfunction "15_15") (pintype "passive"))
      (node (ref "CONT") (pin "16") (pinfunction "16_16") (pintype "passive"))
      (node (ref "CONT") (pin "2") (pinfunction "2_2") (pintype "passive"))
      (node (ref "D1") (pin "1") (pinfunction "Gnd_1") (pintype "passive"))
      (node (ref "D1") (pin "10") (pinfunction "Gnd_10") (pintype "power_in"))
      (node (ref "D1") (pin "3") (pinfunction "Gnd_3") (pintype "power_in"))
      (node (ref "D1") (pin "4") (pinfunction "Gnd_4") (pintype "power_in"))
      (node (ref "D1") (pin "5") (pinfunction "Gnd_5") (pintype "power_in"))
      (node (ref "D1") (pin "6") (pinfunction "Gnd_6") (pintype "power_in"))
      (node (ref "D1") (pin "8") (pinfunction "Gnd_8") (pintype "power_in"))
      (node (ref "D1") (pin "9") (pinfunction "Gnd_9") (pintype "power_in"))
      (node (ref "D2") (pin "1") (pinfunction "Gnd_1") (pintype "passive"))
      (node (ref "D2") (pin "10") (pinfunction "Gnd_10") (pintype "power_in"))
      (node (ref "D2") (pin "3") (pinfunction "Gnd_3") (pintype "power_in"))
      (node (ref "D2") (pin "4") (pinfunction "Gnd_4") (pintype "power_in"))
      (node (ref "D2") (pin "5") (pinfunction "Gnd_5") (pintype "power_in"))
      (node (ref "D2") (pin "6") (pinfunction "Gnd_6") (pintype "power_in"))
      (node (ref "D2") (pin "8") (pinfunction "Gnd_8") (pintype "power_in"))
      (node (ref "D2") (pin "9") (pinfunction "Gnd_9") (pintype "power_in"))
      (node (ref "D3") (pin "1") (pinfunction "Gnd_1") (pintype "passive"))
      (node (ref "D3") (pin "10") (pinfunction "Gnd_10") (pintype "power_in"))
      (node (ref "D3") (pin "3") (pinfunction "Gnd_3") (pintype "power_in"))
      (node (ref "D3") (pin "4") (pinfunction "Gnd_4") (pintype "power_in"))
      (node (ref "D3") (pin "5") (pinfunction "Gnd_5") (pintype "power_in"))
      (node (ref "D3") (pin "6") (pinfunction "Gnd_6") (pintype "power_in"))
      (node (ref "D3") (pin "8") (pinfunction "Gnd_8") (pintype "power_in"))
      (node (ref "D3") (pin "9") (pinfunction "Gnd_9") (pintype "power_in"))
      (node (ref "D4") (pin "1") (pinfunction "Gnd_1") (pintype "passive"))
      (node (ref "D4") (pin "10") (pinfunction "Gnd_10") (pintype "power_in"))
      (node (ref "D4") (pin "3") (pinfunction "Gnd_3") (pintype "power_in"))
      (node (ref "D4") (pin "4") (pinfunction "Gnd_4") (pintype "power_in"))
      (node (ref "D4") (pin "5") (pinfunction "Gnd_5") (pintype "power_in"))
      (node (ref "D4") (pin "6") (pinfunction "Gnd_6") (pintype "power_in"))
      (node (ref "D4") (pin "8") (pinfunction "Gnd_8") (pintype "power_in"))
      (node (ref "D4") (pin "9") (pinfunction "Gnd_9") (pintype "power_in"))
      (node (ref "D5") (pin "1") (pinfunction "Gnd_1") (pintype "passive"))
      (node (ref "D5") (pin "10") (pinfunction "Gnd_10") (pintype "power_in"))
      (node (ref "D5") (pin "3") (pinfunction "Gnd_3") (pintype "power_in"))
      (node (ref "D5") (pin "4") (pinfunction "Gnd_4") (pintype "power_in"))
      (node (ref "D5") (pin "5") (pinfunction "Gnd_5") (pintype "power_in"))
      (node (ref "D5") (pin "6") (pinfunction "Gnd_6") (pintype "power_in"))
      (node (ref "D5") (pin "8") (pinfunction "Gnd_8") (pintype "power_in"))
      (node (ref "D5") (pin "9") (pinfunction "Gnd_9") (pintype "power_in"))
      (node (ref "DP1") (pin "2") (pinfunction "2_2") (pintype "passive"))
      (node (ref "DP10") (pin "2") (pinfunction "2_2") (pintype "passive"))
      (node (ref "DP11") (pin "2") (pinfunction "2_2") (pintype "passive"))
      (node (ref "DP12") (pin "2") (pinfunction "2_2") (pintype "passive"))
      (node (ref "DP13") (pin "2") (pinfunction "2_2") (pintype "passive"))
      (node (ref "DP14") (pin "2") (pinfunction "2_2") (pintype "passive"))
      (node (ref "DP15") (pin "2") (pinfunction "2_2") (pintype "passive"))
      (node (ref "DP16") (pin "2") (pinfunction "2_2") (pintype "passive"))
      (node (ref "DP2") (pin "2") (pinfunction "2_2") (pintype "passive"))
      (node (ref "DP3") (pin "2") (pinfunction "2_2") (pintype "passive"))
      (node (ref "DP4") (pin "2") (pinfunction "2_2") (pintype "passive"))
      (node (ref "DP5") (pin "2") (pinfunction "2_2") (pintype "passive"))
      (node (ref "DP6") (pin "2") (pinfunction "2_2") (pintype "passive"))
      (node (ref "DP7") (pin "2") (pinfunction "2_2") (pintype "passive"))
      (node (ref "DP8") (pin "2") (pinfunction "2_2") (pintype "passive"))
      (node (ref "DP9") (pin "2") (pinfunction "2_2") (pintype "passive"))
      (node (ref "EMI_IN") (pin "2") (pinfunction "GND_2") (pintype "power_in"))
      (node (ref "EMI_IN") (pin "3") (pinfunction "GND_3") (pintype "power_in"))
      (node (ref "EMI_IN") (pin "4") (pinfunction "GND_4") (pintype "power_in"))
      (node (ref "EMI_IN") (pin "5") (pinfunction "GND_5") (pintype "power_in"))
      (node (ref "IN") (pin "2") (pinfunction "GND_2") (pintype "power_in"))
      (node (ref "IN") (pin "3") (pinfunction "GND_3") (pintype "power_in"))
      (node (ref "IN") (pin "4") (pinfunction "GND_4") (pintype "power_in"))
      (node (ref "IN") (pin "5") (pinfunction "GND_5") (pintype "power_in"))
      (node (ref "L1") (pin "5") (pinfunction "CASE_5") (pintype "passive"))
      (node (ref "L2") (pin "5") (pinfunction "CASE_5") (pintype "passive"))
      (node (ref "LC1") (pin "2") (pinfunction "2_2") (pintype "passive"))
      (node (ref "LC10") (pin "2") (pinfunction "2_2") (pintype "passive"))
      (node (ref "LC2") (pin "2") (pinfunction "2_2") (pintype "passive"))
      (node (ref "LC3") (pin "2") (pinfunction "2_2") (pintype "passive"))
      (node (ref "LC4") (pin "2") (pinfunction "2_2") (pintype "passive"))
      (node (ref "LC5") (pin "2") (pinfunction "2_2") (pintype "passive"))
      (node (ref "LC6") (pin "2") (pinfunction "2_2") (pintype "passive"))
      (node (ref "LC7") (pin "2") (pinfunction "2_2") (pintype "passive"))
      (node (ref "LC8") (pin "2") (pinfunction "2_2") (pintype "passive"))
      (node (ref "LC9") (pin "2") (pinfunction "2_2") (pintype "passive"))
      (node (ref "N1") (pin "2") (pinfunction "A_2") (pintype "passive"))
      (node (ref "OSC") (pin "2") (pinfunction "GND_2") (pintype "power_in"))
      (node (ref "OSC") (pin "3") (pinfunction "GND_3") (pintype "power_in"))
      (node (ref "OSC") (pin "4") (pinfunction "GND_4") (pintype "power_in"))
      (node (ref "OSC") (pin "5") (pinfunction "GND_5") (pintype "power_in"))
      (node (ref "OUT") (pin "2") (pinfunction "GND_2") (pintype "power_in"))
      (node (ref "OUT") (pin "3") (pinfunction "GND_3") (pintype "power_in"))
      (node (ref "OUT") (pin "4") (pinfunction "GND_4") (pintype "power_in"))
      (node (ref "OUT") (pin "5") (pinfunction "GND_5") (pintype "power_in"))
      (node (ref "R1") (pin "1") (pinfunction "1_1") (pintype "passive"))
      (node (ref "R2") (pin "1") (pinfunction "1_1") (pintype "passive"))
      (node (ref "T2-A") (pin "2") (pinfunction "GND_2") (pintype "power_in"))
      (node (ref "T2-A") (pin "3") (pinfunction "GND_3") (pintype "power_in"))
      (node (ref "T2-A") (pin "4") (pinfunction "GND_4") (pintype "power_in"))
      (node (ref "T2-A") (pin "5") (pinfunction "GND_5") (pintype "power_in"))
      (node (ref "T2-B") (pin "2") (pinfunction "GND_2") (pintype "power_in"))
      (node (ref "T2-B") (pin "3") (pinfunction "GND_3") (pintype "power_in"))
      (node (ref "T2-B") (pin "4") (pinfunction "GND_4") (pintype "power_in"))
      (node (ref "T2-B") (pin "5") (pinfunction "GND_5") (pintype "power_in"))
      (node (ref "TONE") (pin "2") (pinfunction "GND_2") (pintype "power_in"))
      (node (ref "TONE") (pin "3") (pinfunction "GND_3") (pintype "power_in"))
      (node (ref "TONE") (pin "4") (pinfunction "GND_4") (pintype "power_in"))
      (node (ref "TONE") (pin "5") (pinfunction "GND_5") (pintype "power_in"))
      (node (ref "U1") (pin "2") (pinfunction "Gnd_2") (pintype "power_in"))
      (node (ref "U10") (pin "13") (pinfunction "~{OE}_13") (pintype "input"))
      (node (ref "U10") (pin "8") (pinfunction "GND_8") (pintype "power_in"))
      (node (ref "U2") (pin "15") (pinfunction "Paddle_15") (pintype "power_in"))
      (node (ref "U3") (pin "1") (pinfunction "Gnd_1") (pintype "passive"))
      (node (ref "U3") (pin "10") (pinfunction "Gnd_10") (pintype "power_in"))
      (node (ref "U3") (pin "3") (pinfunction "Gnd_3") (pintype "power_in"))
      (node (ref "U3") (pin "4") (pinfunction "Gnd_4") (pintype "power_in"))
      (node (ref "U3") (pin "5") (pinfunction "Gnd_5") (pintype "power_in"))
      (node (ref "U3") (pin "6") (pinfunction "Gnd_6") (pintype "power_in"))
      (node (ref "U3") (pin "8") (pinfunction "Gnd_8") (pintype "power_in"))
      (node (ref "U3") (pin "9") (pinfunction "Gnd_9") (pintype "power_in"))
      (node (ref "U4") (pin "1") (pinfunction "Gnd_1") (pintype "passive"))
      (node (ref "U4") (pin "10") (pinfunction "Gnd_10") (pintype "power_in"))
      (node (ref "U4") (pin "3") (pinfunction "Gnd_3") (pintype "power_in"))
      (node (ref "U4") (pin "4") (pinfunction "Gnd_4") (pintype "power_in"))
      (node (ref "U4") (pin "5") (pinfunction "Gnd_5") (pintype "power_in"))
      (node (ref "U4") (pin "6") (pinfunction "Gnd_6") (pintype "power_in"))
      (node (ref "U4") (pin "8") (pinfunction "Gnd_8") (pintype "power_in"))
      (node (ref "U4") (pin "9") (pinfunction "Gnd_9") (pintype "power_in"))
      (node (ref "U8") (pin "15") (pinfunction "Paddle_15") (pintype "power_in"))
    )
    (net (code "31") (name "Net-(C1-Pad1)") (class "Default")
      (node (ref "C1") (pin "1") (pinfunction "1_1") (pintype "passive"))
      (node (ref "D1") (pin "7") (pinfunction "Gnd_7") (pintype "output"))
    )
    (net (code "32") (name "Net-(C4-Pad1)") (class "Default")
      (node (ref "C4") (pin "1") (pinfunction "1_1") (pintype "passive"))
      (node (ref "R2") (pin "2") (pinfunction "2_2") (pintype "passive"))
    )
    (net (code "33") (name "Net-(C7-Pad1)") (class "Default")
      (node (ref "C7") (pin "1") (pinfunction "1_1") (pintype "passive"))
      (node (ref "D3") (pin "7") (pinfunction "Gnd_7") (pintype "output"))
    )
    (net (code "34") (name "Net-(C27-Pad1)") (class "Default")
      (node (ref "C27") (pin "1") (pinfunction "1_1") (pintype "passive"))
      (node (ref "D5") (pin "7") (pinfunction "Gnd_7") (pintype "output"))
    )
    (net (code "35") (name "Net-(D1-In)") (class "Default")
      (node (ref "D1") (pin "2") (pinfunction "In_2") (pintype "input"))
      (node (ref "TONE") (pin "1") (pinfunction "Signal_1") (pintype "passive"))
    )
    (net (code "36") (name "Net-(D2-In)") (class "Default")
      (node (ref "D2") (pin "2") (pinfunction "In_2") (pintype "input"))
      (node (ref "IN") (pin "1") (pinfunction "Signal_1") (pintype "passive"))
    )
    (net (code "37") (name "Net-(D3-In)") (class "Default")
      (node (ref "D3") (pin "2") (pinfunction "In_2") (pintype "input"))
      (node (ref "EMI_IN") (pin "1") (pinfunction "Signal_1") (pintype "passive"))
    )
    (net (code "38") (name "Net-(D4-In)") (class "Default")
      (node (ref "D4") (pin "2") (pinfunction "In_2") (pintype "input"))
      (node (ref "L2") (pin "2") (pinfunction "RF_2") (pintype "passive"))
    )
    (net (code "39") (name "Net-(D5-In)") (class "Default")
      (node (ref "D5") (pin "2") (pinfunction "In_2") (pintype "input"))
      (node (ref "OSC") (pin "1") (pinfunction "Signal_1") (pintype "passive"))
    )
    (net (code "40") (name "Net-(DP1-Pad1)") (class "Default")
      (node (ref "DP1") (pin "1") (pinfunction "1_1") (pintype "passive"))
      (node (ref "RL1") (pin "2") (pinfunction "2_2") (pintype "passive"))
    )
    (net (code "41") (name "Net-(DP2-Pad1)") (class "Default")
      (node (ref "DP2") (pin "1") (pinfunction "1_1") (pintype "passive"))
      (node (ref "RL2") (pin "2") (pinfunction "2_2") (pintype "passive"))
    )
    (net (code "42") (name "Net-(DP3-Pad1)") (class "Default")
      (node (ref "DP3") (pin "1") (pinfunction "1_1") (pintype "passive"))
      (node (ref "RL3") (pin "2") (pinfunction "2_2") (pintype "passive"))
    )
    (net (code "43") (name "Net-(DP4-Pad1)") (class "Default")
      (node (ref "DP4") (pin "1") (pinfunction "1_1") (pintype "passive"))
      (node (ref "RL4") (pin "2") (pinfunction "2_2") (pintype "passive"))
    )
    (net (code "44") (name "Net-(DP5-Pad1)") (class "Default")
      (node (ref "DP5") (pin "1") (pinfunction "1_1") (pintype "passive"))
      (node (ref "RL5") (pin "2") (pinfunction "2_2") (pintype "passive"))
    )
    (net (code "45") (name "Net-(DP6-Pad1)") (class "Default")
      (node (ref "DP6") (pin "1") (pinfunction "1_1") (pintype "passive"))
      (node (ref "RL6") (pin "2") (pinfunction "2_2") (pintype "passive"))
    )
    (net (code "46") (name "Net-(DP7-Pad1)") (class "Default")
      (node (ref "DP7") (pin "1") (pinfunction "1_1") (pintype "passive"))
      (node (ref "RL7") (pin "2") (pinfunction "2_2") (pintype "passive"))
    )
    (net (code "47") (name "Net-(DP8-Pad1)") (class "Default")
      (node (ref "DP8") (pin "1") (pinfunction "1_1") (pintype "passive"))
      (node (ref "RL8") (pin "2") (pinfunction "2_2") (pintype "passive"))
    )
    (net (code "48") (name "Net-(DP9-Pad1)") (class "Default")
      (node (ref "DP9") (pin "1") (pinfunction "1_1") (pintype "passive"))
      (node (ref "RL9") (pin "2") (pinfunction "2_2") (pintype "passive"))
    )
    (net (code "49") (name "Net-(DP10-Pad1)") (class "Default")
      (node (ref "DP10") (pin "1") (pinfunction "1_1") (pintype "passive"))
      (node (ref "RL10") (pin "2") (pinfunction "2_2") (pintype "passive"))
    )
    (net (code "50") (name "Net-(DP11-Pad1)") (class "Default")
      (node (ref "DP11") (pin "1") (pinfunction "1_1") (pintype "passive"))
      (node (ref "RL11") (pin "2") (pinfunction "2_2") (pintype "passive"))
    )
    (net (code "51") (name "Net-(DP12-Pad1)") (class "Default")
      (node (ref "DP12") (pin "1") (pinfunction "1_1") (pintype "passive"))
      (node (ref "RL12") (pin "2") (pinfunction "2_2") (pintype "passive"))
    )
    (net (code "52") (name "Net-(DP13-Pad1)") (class "Default")
      (node (ref "DP13") (pin "1") (pinfunction "1_1") (pintype "passive"))
      (node (ref "RL13") (pin "2") (pinfunction "2_2") (pintype "passive"))
    )
    (net (code "53") (name "Net-(DP14-Pad1)") (class "Default")
      (node (ref "DP14") (pin "1") (pinfunction "1_1") (pintype "passive"))
      (node (ref "RL14") (pin "2") (pinfunction "2_2") (pintype "passive"))
    )
    (net (code "54") (name "Net-(DP15-Pad1)") (class "Default")
      (node (ref "DP15") (pin "1") (pinfunction "1_1") (pintype "passive"))
      (node (ref "RL15") (pin "2") (pinfunction "2_2") (pintype "passive"))
    )
    (net (code "55") (name "Net-(DP16-Pad1)") (class "Default")
      (node (ref "DP16") (pin "1") (pinfunction "1_1") (pintype "passive"))
      (node (ref "RL16") (pin "2") (pinfunction "2_2") (pintype "passive"))
    )
    (net (code "56") (name "Net-(L1-RF+DC)") (class "Default")
      (node (ref "L1") (pin "1") (pinfunction "RF+DC_1") (pintype "passive"))
      (node (ref "U3") (pin "7") (pinfunction "Gnd_7") (pintype "output"))
    )
    (net (code "57") (name "Net-(L2-RF+DC)") (class "Default")
      (node (ref "L2") (pin "1") (pinfunction "RF+DC_1") (pintype "passive"))
      (node (ref "U4") (pin "7") (pinfunction "Gnd_7") (pintype "output"))
    )
    (net (code "58") (name "Net-(N1-C)") (class "Default")
      (node (ref "C5") (pin "1") (pinfunction "1_1") (pintype "passive"))
      (node (ref "N1") (pin "3") (pinfunction "C_3") (pintype "passive"))
      (node (ref "R3") (pin "1") (pinfunction "1_1") (pintype "passive"))
    )
    (net (code "59") (name "Net-(OUT-Signal)") (class "Default")
      (node (ref "D4") (pin "7") (pinfunction "Gnd_7") (pintype "output"))
      (node (ref "OUT") (pin "1") (pinfunction "Signal_1") (pintype "passive"))
    )
    (net (code "60") (name "Net-(T2-A-Signal)") (class "Default")
      (node (ref "T2-A") (pin "1") (pinfunction "Signal_1") (pintype "passive"))
      (node (ref "T2-B") (pin "1") (pinfunction "Signal_1") (pintype "passive"))
    )
    (net (code "61") (name "Net-(U1-Coupled)") (class "Default")
      (node (ref "C16") (pin "2") (pinfunction "2_2") (pintype "passive"))
      (node (ref "U1") (pin "3") (pinfunction "Coupled_3") (pintype "output"))
    )
    (net (code "62") (name "Net-(U1-Input)") (class "Default")
      (node (ref "D2") (pin "7") (pinfunction "Gnd_7") (pintype "output"))
      (node (ref "U1") (pin "1") (pinfunction "Input_1") (pintype "input"))
    )
    (net (code "63") (name "Net-(U1-Output)") (class "Default")
      (node (ref "C3") (pin "1") (pinfunction "1_1") (pintype "passive"))
      (node (ref "U1") (pin "6") (pinfunction "Output_6") (pintype "output"))
    )
    (net (code "64") (name "Net-(U1-Termination)") (class "Default")
      (node (ref "R1") (pin "2") (pinfunction "2_2") (pintype "passive"))
      (node (ref "U1") (pin "4") (pinfunction "Termination_4") (pintype "output"))
    )
    (net (code "65") (name "Net-(U2-IN1)") (class "Default")
      (node (ref "R23") (pin "1") (pinfunction "1_1") (pintype "passive"))
      (node (ref "U2") (pin "7") (pinfunction "IN1_7") (pintype "input"))
    )
    (net (code "66") (name "Net-(U2-IN2)") (class "Default")
      (node (ref "R22") (pin "1") (pinfunction "1_1") (pintype "passive"))
      (node (ref "U2") (pin "6") (pinfunction "IN2_6") (pintype "input"))
    )
    (net (code "67") (name "Net-(U2-IN3)") (class "Default")
      (node (ref "R21") (pin "1") (pinfunction "1_1") (pintype "passive"))
      (node (ref "U2") (pin "5") (pinfunction "IN3_5") (pintype "input"))
    )
    (net (code "68") (name "Net-(U2-RF1)") (class "Default")
      (node (ref "C3") (pin "2") (pinfunction "2_2") (pintype "passive"))
      (node (ref "U2") (pin "3") (pinfunction "RF1_3") (pintype "passive"))
    )
    (net (code "69") (name "Net-(U2-RF2)") (class "Default")
      (node (ref "C19") (pin "2") (pinfunction "2_2") (pintype "passive"))
      (node (ref "U2") (pin "9") (pinfunction "RF2_9") (pintype "passive"))
    )
    (net (code "70") (name "Net-(U2-RF3)") (class "Default")
      (node (ref "C7") (pin "2") (pinfunction "2_2") (pintype "passive"))
      (node (ref "U2") (pin "2") (pinfunction "RF3_2") (pintype "passive"))
    )
    (net (code "71") (name "Net-(U2-RF4)") (class "Default")
      (node (ref "C2") (pin "2") (pinfunction "2_2") (pintype "passive"))
      (node (ref "U2") (pin "10") (pinfunction "RF4_10") (pintype "passive"))
    )
    (net (code "72") (name "Net-(U2-RF5)") (class "Default")
      (node (ref "C4") (pin "2") (pinfunction "2_2") (pintype "passive"))
      (node (ref "U2") (pin "1") (pinfunction "RF5_1") (pintype "passive"))
    )
    (net (code "73") (name "Net-(U2-RF6)") (class "Default")
      (node (ref "C6") (pin "2") (pinfunction "2_2") (pintype "passive"))
      (node (ref "U2") (pin "11") (pinfunction "RF6_11") (pintype "passive"))
    )
    (net (code "74") (name "Net-(U2-RF_COM)") (class "Default")
      (node (ref "C8") (pin "1") (pinfunction "1_1") (pintype "passive"))
      (node (ref "U2") (pin "13") (pinfunction "RF_COM_13") (pintype "passive"))
    )
    (net (code "75") (name "Net-(U2-Vdd)") (class "Default")
      (node (ref "R20") (pin "1") (pinfunction "1_1") (pintype "passive"))
      (node (ref "U2") (pin "4") (pinfunction "Vdd_4") (pintype "power_in"))
    )
    (net (code "76") (name "Net-(U3-In)") (class "Default")
      (node (ref "C8") (pin "2") (pinfunction "2_2") (pintype "passive"))
      (node (ref "U3") (pin "2") (pinfunction "In_2") (pintype "input"))
    )
    (net (code "77") (name "Net-(U4-In)") (class "Default")
      (node (ref "C14") (pin "2") (pinfunction "2_2") (pintype "passive"))
      (node (ref "U4") (pin "2") (pinfunction "In_2") (pintype "input"))
    )
    (net (code "78") (name "Net-(U8-IN1)") (class "Default")
      (node (ref "R26") (pin "2") (pinfunction "2_2") (pintype "passive"))
      (node (ref "U8") (pin "7") (pinfunction "IN1_7") (pintype "input"))
    )
    (net (code "79") (name "Net-(U8-IN2)") (class "Default")
      (node (ref "R25") (pin "2") (pinfunction "2_2") (pintype "passive"))
      (node (ref "U8") (pin "6") (pinfunction "IN2_6") (pintype "input"))
    )
    (net (code "80") (name "Net-(U8-IN3)") (class "Default")
      (node (ref "R24") (pin "2") (pinfunction "2_2") (pintype "passive"))
      (node (ref "U8") (pin "5") (pinfunction "IN3_5") (pintype "input"))
    )
    (net (code "81") (name "Net-(U8-RF5)") (class "Default")
      (node (ref "C17") (pin "1") (pinfunction "1_1") (pintype "passive"))
      (node (ref "U8") (pin "1") (pinfunction "RF5_1") (pintype "passive"))
    )
    (net (code "82") (name "Net-(U8-RF6)") (class "Default")
      (node (ref "C15") (pin "1") (pinfunction "1_1") (pintype "passive"))
      (node (ref "U8") (pin "11") (pinfunction "RF6_11") (pintype "passive"))
    )
    (net (code "83") (name "Net-(U8-RF_COM)") (class "Default")
      (node (ref "C27") (pin "2") (pinfunction "2_2") (pintype "passive"))
      (node (ref "U8") (pin "13") (pinfunction "RF_COM_13") (pintype "passive"))
    )
    (net (code "84") (name "Net-(U8-Vdd)") (class "Default")
      (node (ref "R31") (pin "1") (pinfunction "1_1") (pintype "passive"))
      (node (ref "U8") (pin "4") (pinfunction "Vdd_4") (pintype "power_in"))
    )
    (net (code "85") (name "Net-(U10-QA)") (class "Default")
      (node (ref "C21") (pin "2") (pinfunction "2_2") (pintype "passive"))
      (node (ref "R21") (pin "2") (pinfunction "2_2") (pintype "passive"))
      (node (ref "RL1") (pin "1") (pinfunction "1_1") (pintype "passive"))
      (node (ref "U10") (pin "15") (pinfunction "QA_15") (pintype "tri_state"))
    )
    (net (code "86") (name "Net-(U10-QB)") (class "Default")
      (node (ref "C22") (pin "2") (pinfunction "2_2") (pintype "passive"))
      (node (ref "R22") (pin "2") (pinfunction "2_2") (pintype "passive"))
      (node (ref "RL2") (pin "1") (pinfunction "1_1") (pintype "passive"))
      (node (ref "U10") (pin "1") (pinfunction "QB_1") (pintype "tri_state"))
    )
    (net (code "87") (name "Net-(U10-QC)") (class "Default")
      (node (ref "C23") (pin "2") (pinfunction "2_2") (pintype "passive"))
      (node (ref "R23") (pin "2") (pinfunction "2_2") (pintype "passive"))
      (node (ref "RL3") (pin "1") (pinfunction "1_1") (pintype "passive"))
      (node (ref "U10") (pin "2") (pinfunction "QC_2") (pintype "tri_state"))
    )
    (net (code "88") (name "Net-(U10-QD)") (class "Default")
      (node (ref "C26") (pin "2") (pinfunction "2_2") (pintype "passive"))
      (node (ref "R26") (pin "1") (pinfunction "1_1") (pintype "passive"))
      (node (ref "RL4") (pin "1") (pinfunction "1_1") (pintype "passive"))
      (node (ref "U10") (pin "3") (pinfunction "QD_3") (pintype "tri_state"))
    )
    (net (code "89") (name "Net-(U10-QE)") (class "Default")
      (node (ref "C25") (pin "2") (pinfunction "2_2") (pintype "passive"))
      (node (ref "R25") (pin "1") (pinfunction "1_1") (pintype "passive"))
      (node (ref "RL5") (pin "1") (pinfunction "1_1") (pintype "passive"))
      (node (ref "U10") (pin "4") (pinfunction "QE_4") (pintype "tri_state"))
    )
    (net (code "90") (name "Net-(U10-QF)") (class "Default")
      (node (ref "C24") (pin "2") (pinfunction "2_2") (pintype "passive"))
      (node (ref "R24") (pin "1") (pinfunction "1_1") (pintype "passive"))
      (node (ref "RL6") (pin "1") (pinfunction "1_1") (pintype "passive"))
      (node (ref "U10") (pin "5") (pinfunction "QF_5") (pintype "tri_state"))
    )
    (net (code "91") (name "Net-(U10-QG)") (class "Default")
      (node (ref "RL7") (pin "1") (pinfunction "1_1") (pintype "passive"))
      (node (ref "U10") (pin "6") (pinfunction "QG_6") (pintype "tri_state"))
    )
    (net (code "92") (name "Net-(U10-QH)") (class "Default")
      (node (ref "RL8") (pin "1") (pinfunction "1_1") (pintype "passive"))
      (node (ref "U10") (pin "7") (pinfunction "QH_7") (pintype "tri_state"))
    )
    (net (code "93") (name "Net-(U10-RCLK)") (class "Default")
      (node (ref "LC5") (pin "1") (pinfunction "1_1") (pintype "passive"))
      (node (ref "RL11") (pin "1") (pinfunction "1_1") (pintype "passive"))
      (node (ref "U10") (pin "12") (pinfunction "RCLK_12") (pintype "input"))
    )
    (net (code "94") (name "unconnected-(L1-NC-Pad4)") (class "Default")
      (node (ref "L1") (pin "4") (pinfunction "NC_4") (pintype "passive"))
    )
    (net (code "95") (name "unconnected-(L2-NC-Pad4)") (class "Default")
      (node (ref "L2") (pin "4") (pinfunction "NC_4") (pintype "passive"))
    )
    (net (code "96") (name "unconnected-(U1-DNC-Pad5)") (class "Default")
      (node (ref "U1") (pin "5") (pinfunction "DNC_5") (pintype "passive"))
    )
    (net (code "97") (name "unconnected-(U2-NC-Pad8)") (class "Default")
      (node (ref "U2") (pin "8") (pinfunction "NC_8") (pintype "passive+no_connect"))
    )
    (net (code "98") (name "unconnected-(U2-NC-Pad12)") (class "Default")
      (node (ref "U2") (pin "12") (pinfunction "NC_12") (pintype "passive+no_connect"))
    )
    (net (code "99") (name "unconnected-(U2-NC-Pad14)") (class "Default")
      (node (ref "U2") (pin "14") (pinfunction "NC_14") (pintype "passive+no_connect"))
    )
    (net (code "100") (name "unconnected-(U8-NC-Pad8)") (class "Default")
      (node (ref "U8") (pin "8") (pinfunction "NC_8") (pintype "passive"))
    )
    (net (code "101") (name "unconnected-(U8-NC-Pad12)") (class "Default")
      (node (ref "U8") (pin "12") (pinfunction "NC_12") (pintype "passive"))
    )
    (net (code "102") (name "unconnected-(U8-NC-Pad14)") (class "Default")
      (node (ref "U8") (pin "14") (pinfunction "NC_14") (pintype "passive"))
    )
    (net (code "103") (name "unconnected-(U8-RF1-Pad3)") (class "Default")
      (node (ref "U8") (pin "3") (pinfunction "RF1_3") (pintype "passive"))
    )
    (net (code "104") (name "unconnected-(U8-RF2-Pad9)") (class "Default")
      (node (ref "U8") (pin "9") (pinfunction "RF2_9") (pintype "passive"))
    )
    (net (code "105") (name "unconnected-(U8-RF3-Pad2)") (class "Default")
      (node (ref "U8") (pin "2") (pinfunction "RF3_2") (pintype "passive"))
    )
    (net (code "106") (name "unconnected-(U8-RF4-Pad10)") (class "Default")
      (node (ref "U8") (pin "10") (pinfunction "RF4_10") (pintype "passive"))
    )
    (net (code "107") (name "unconnected-(U10-QH'-Pad9)") (class "Default")
      (node (ref "U10") (pin "9") (pinfunction "QH'_9") (pintype "output"))
    )
  )
)
